# picotouch_synth.net
KiCad netlist of a schematic drawn in EAGLE
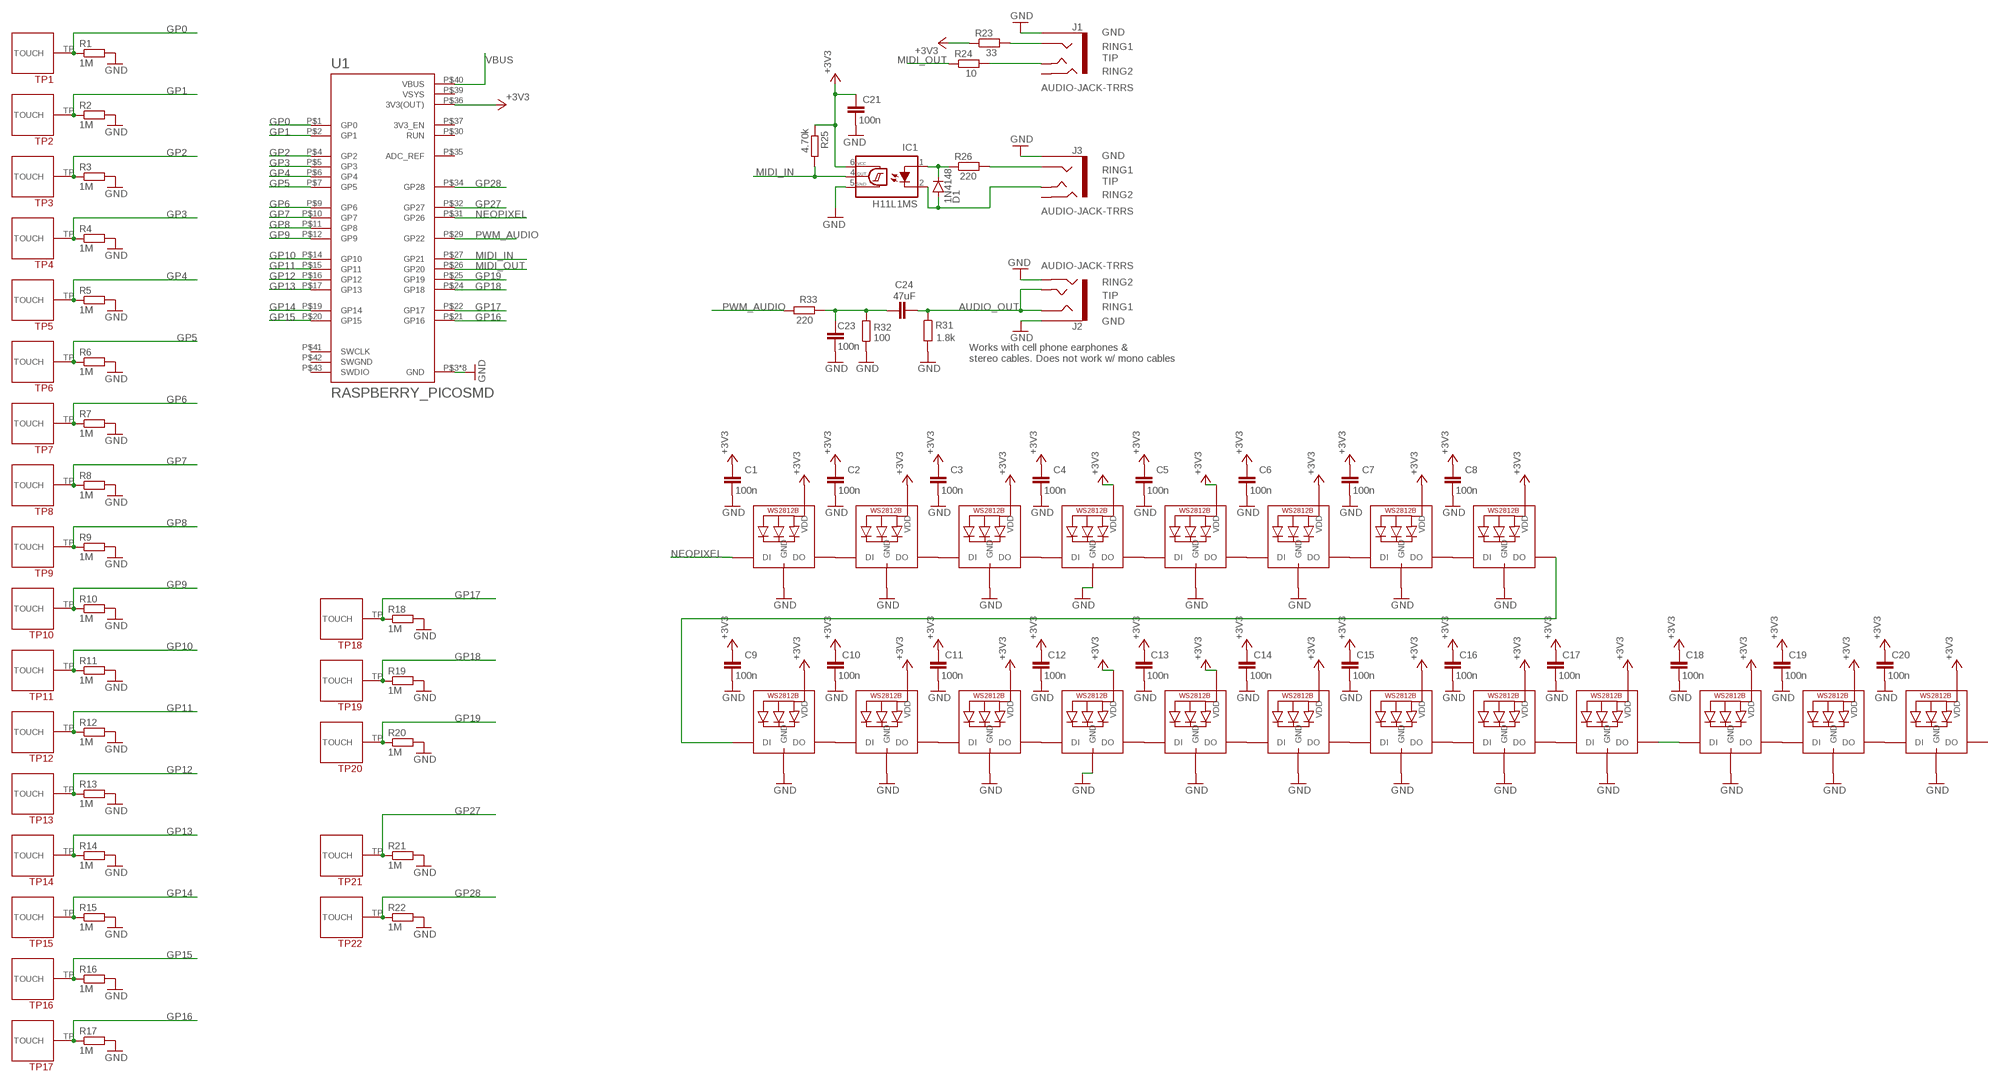
[diagram p0: schematic, sheet 1]

(export (version "E")
  (design (tool "Eeschema 10.0.6"))
  (components
    (comp (ref "C1")
      (value "100n")
      (footprint "eagle-import:C0603")
      (libsource (lib "eagle-import") (part "C-EUC0603"))
    )
    (comp (ref "C2")
      (value "100n")
      (footprint "eagle-import:C0603")
      (libsource (lib "eagle-import") (part "C-EUC0603"))
    )
    (comp (ref "C3")
      (value "100n")
      (footprint "eagle-import:C0603")
      (libsource (lib "eagle-import") (part "C-EUC0603"))
    )
    (comp (ref "C4")
      (value "100n")
      (footprint "eagle-import:C0603")
      (libsource (lib "eagle-import") (part "C-EUC0603"))
    )
    (comp (ref "C5")
      (value "100n")
      (footprint "eagle-import:C0603")
      (libsource (lib "eagle-import") (part "C-EUC0603"))
    )
    (comp (ref "C6")
      (value "100n")
      (footprint "eagle-import:C0603")
      (libsource (lib "eagle-import") (part "C-EUC0603"))
    )
    (comp (ref "C7")
      (value "100n")
      (footprint "eagle-import:C0603")
      (libsource (lib "eagle-import") (part "C-EUC0603"))
    )
    (comp (ref "C8")
      (value "100n")
      (footprint "eagle-import:C0603")
      (libsource (lib "eagle-import") (part "C-EUC0603"))
    )
    (comp (ref "C9")
      (value "100n")
      (footprint "eagle-import:C0603")
      (libsource (lib "eagle-import") (part "C-EUC0603"))
    )
    (comp (ref "C10")
      (value "100n")
      (footprint "eagle-import:C0603")
      (libsource (lib "eagle-import") (part "C-EUC0603"))
    )
    (comp (ref "C11")
      (value "100n")
      (footprint "eagle-import:C0603")
      (libsource (lib "eagle-import") (part "C-EUC0603"))
    )
    (comp (ref "C12")
      (value "100n")
      (footprint "eagle-import:C0603")
      (libsource (lib "eagle-import") (part "C-EUC0603"))
    )
    (comp (ref "C13")
      (value "100n")
      (footprint "eagle-import:C0603")
      (libsource (lib "eagle-import") (part "C-EUC0603"))
    )
    (comp (ref "C14")
      (value "100n")
      (footprint "eagle-import:C0603")
      (libsource (lib "eagle-import") (part "C-EUC0603"))
    )
    (comp (ref "C15")
      (value "100n")
      (footprint "eagle-import:C0603")
      (libsource (lib "eagle-import") (part "C-EUC0603"))
    )
    (comp (ref "C16")
      (value "100n")
      (footprint "eagle-import:C0603")
      (libsource (lib "eagle-import") (part "C-EUC0603"))
    )
    (comp (ref "C17")
      (value "100n")
      (footprint "eagle-import:C0603")
      (libsource (lib "eagle-import") (part "C-EUC0603"))
    )
    (comp (ref "C18")
      (value "100n")
      (footprint "eagle-import:C0603")
      (libsource (lib "eagle-import") (part "C-EUC0603"))
    )
    (comp (ref "C19")
      (value "100n")
      (footprint "eagle-import:C0603")
      (libsource (lib "eagle-import") (part "C-EUC0603"))
    )
    (comp (ref "C20")
      (value "100n")
      (footprint "eagle-import:C0603")
      (libsource (lib "eagle-import") (part "C-EUC0603"))
    )
    (comp (ref "C21")
      (value "100n")
      (footprint "eagle-import:C0603")
      (libsource (lib "eagle-import") (part "C-EUC0603"))
    )
    (comp (ref "C23")
      (value "100n")
      (footprint "eagle-import:C0603")
      (libsource (lib "eagle-import") (part "C-EUC0603"))
    )
    (comp (ref "C24")
      (value "47uF")
      (footprint "eagle-import:C0603")
      (libsource (lib "eagle-import") (part "C-EUC0603"))
    )
    (comp (ref "D1")
      (value "1N4148")
      (footprint "eagle-import:SOD123")
      (libsource (lib "eagle-import") (part "DIODE-SOD123"))
    )
    (comp (ref "IC1")
      (value "H11L1MS")
      (footprint "eagle-import:DIL6-SMD")
      (libsource (lib "eagle-import") (part "H11LMS1"))
    )
    (comp (ref "J1")
      (value "AUDIO-JACK-TRRS")
      (footprint "eagle-import:PJ-320D_SPARKFUN")
      (fields (field (name "MPN") "PJ-320D"))
      (libsource (lib "eagle-import") (part "AUDIO-JACK-TRRS"))
    )
    (comp (ref "J2")
      (value "AUDIO-JACK-TRRS")
      (footprint "eagle-import:PJ-320D_SPARKFUN")
      (fields (field (name "MPN") "PJ-320D") (field (name "LCSC") "C431535"))
      (libsource (lib "eagle-import") (part "AUDIO-JACK-TRRS"))
    )
    (comp (ref "J3")
      (value "AUDIO-JACK-TRRS")
      (footprint "eagle-import:PJ-320D_SPARKFUN")
      (fields (field (name "MPN") "PJ-320D"))
      (libsource (lib "eagle-import") (part "AUDIO-JACK-TRRS"))
    )
    (comp (ref "LED1")
      (value "WS2812B3535")
      (footprint "eagle-import:LED3535")
      (libsource (lib "eagle-import") (part "WS2812B3535"))
    )
    (comp (ref "LED2")
      (value "WS2812B3535")
      (footprint "eagle-import:LED3535")
      (libsource (lib "eagle-import") (part "WS2812B3535"))
    )
    (comp (ref "LED3")
      (value "WS2812B3535")
      (footprint "eagle-import:LED3535")
      (libsource (lib "eagle-import") (part "WS2812B3535"))
    )
    (comp (ref "LED4")
      (value "WS2812B3535")
      (footprint "eagle-import:LED3535")
      (libsource (lib "eagle-import") (part "WS2812B3535"))
    )
    (comp (ref "LED5")
      (value "WS2812B3535")
      (footprint "eagle-import:LED3535")
      (libsource (lib "eagle-import") (part "WS2812B3535"))
    )
    (comp (ref "LED6")
      (value "WS2812B3535")
      (footprint "eagle-import:LED3535")
      (libsource (lib "eagle-import") (part "WS2812B3535"))
    )
    (comp (ref "LED7")
      (value "WS2812B3535")
      (footprint "eagle-import:LED3535")
      (libsource (lib "eagle-import") (part "WS2812B3535"))
    )
    (comp (ref "LED8")
      (value "WS2812B3535")
      (footprint "eagle-import:LED3535")
      (libsource (lib "eagle-import") (part "WS2812B3535"))
    )
    (comp (ref "LED9")
      (value "WS2812B3535")
      (footprint "eagle-import:LED3535")
      (libsource (lib "eagle-import") (part "WS2812B3535"))
    )
    (comp (ref "LED10")
      (value "WS2812B3535")
      (footprint "eagle-import:LED3535")
      (libsource (lib "eagle-import") (part "WS2812B3535"))
    )
    (comp (ref "LED11")
      (value "WS2812B3535")
      (footprint "eagle-import:LED3535")
      (libsource (lib "eagle-import") (part "WS2812B3535"))
    )
    (comp (ref "LED12")
      (value "WS2812B3535")
      (footprint "eagle-import:LED3535")
      (libsource (lib "eagle-import") (part "WS2812B3535"))
    )
    (comp (ref "LED13")
      (value "WS2812B3535")
      (footprint "eagle-import:LED3535")
      (libsource (lib "eagle-import") (part "WS2812B3535"))
    )
    (comp (ref "LED14")
      (value "WS2812B3535")
      (footprint "eagle-import:LED3535")
      (libsource (lib "eagle-import") (part "WS2812B3535"))
    )
    (comp (ref "LED15")
      (value "WS2812B3535")
      (footprint "eagle-import:LED3535")
      (libsource (lib "eagle-import") (part "WS2812B3535"))
    )
    (comp (ref "LED16")
      (value "WS2812B3535")
      (footprint "eagle-import:LED3535")
      (libsource (lib "eagle-import") (part "WS2812B3535"))
    )
    (comp (ref "LED17")
      (value "WS2812B3535")
      (footprint "eagle-import:LED3535")
      (libsource (lib "eagle-import") (part "WS2812B3535"))
    )
    (comp (ref "LED18")
      (value "WS2812B3535")
      (footprint "eagle-import:LED3535")
      (libsource (lib "eagle-import") (part "WS2812B3535"))
    )
    (comp (ref "LED19")
      (value "WS2812B3535")
      (footprint "eagle-import:LED3535")
      (libsource (lib "eagle-import") (part "WS2812B3535"))
    )
    (comp (ref "LED20")
      (value "WS2812B3535")
      (footprint "eagle-import:LED3535")
      (libsource (lib "eagle-import") (part "WS2812B3535"))
    )
    (comp (ref "R1")
      (value "1M")
      (footprint "eagle-import:R0805")
      (libsource (lib "eagle-import") (part "R-EU_R0805"))
    )
    (comp (ref "R2")
      (value "1M")
      (footprint "eagle-import:R0805")
      (libsource (lib "eagle-import") (part "R-EU_R0805"))
    )
    (comp (ref "R3")
      (value "1M")
      (footprint "eagle-import:R0805")
      (libsource (lib "eagle-import") (part "R-EU_R0805"))
    )
    (comp (ref "R4")
      (value "1M")
      (footprint "eagle-import:R0805")
      (libsource (lib "eagle-import") (part "R-EU_R0805"))
    )
    (comp (ref "R5")
      (value "1M")
      (footprint "eagle-import:R0805")
      (libsource (lib "eagle-import") (part "R-EU_R0805"))
    )
    (comp (ref "R6")
      (value "1M")
      (footprint "eagle-import:R0805")
      (libsource (lib "eagle-import") (part "R-EU_R0805"))
    )
    (comp (ref "R7")
      (value "1M")
      (footprint "eagle-import:R0805")
      (libsource (lib "eagle-import") (part "R-EU_R0805"))
    )
    (comp (ref "R8")
      (value "1M")
      (footprint "eagle-import:R0805")
      (libsource (lib "eagle-import") (part "R-EU_R0805"))
    )
    (comp (ref "R9")
      (value "1M")
      (footprint "eagle-import:R0805")
      (libsource (lib "eagle-import") (part "R-EU_R0805"))
    )
    (comp (ref "R10")
      (value "1M")
      (footprint "eagle-import:R0805")
      (libsource (lib "eagle-import") (part "R-EU_R0805"))
    )
    (comp (ref "R11")
      (value "1M")
      (footprint "eagle-import:R0805")
      (libsource (lib "eagle-import") (part "R-EU_R0805"))
    )
    (comp (ref "R12")
      (value "1M")
      (footprint "eagle-import:R0805")
      (libsource (lib "eagle-import") (part "R-EU_R0805"))
    )
    (comp (ref "R13")
      (value "1M")
      (footprint "eagle-import:R0805")
      (libsource (lib "eagle-import") (part "R-EU_R0805"))
    )
    (comp (ref "R14")
      (value "1M")
      (footprint "eagle-import:R0805")
      (libsource (lib "eagle-import") (part "R-EU_R0805"))
    )
    (comp (ref "R15")
      (value "1M")
      (footprint "eagle-import:R0805")
      (libsource (lib "eagle-import") (part "R-EU_R0805"))
    )
    (comp (ref "R16")
      (value "1M")
      (footprint "eagle-import:R0805")
      (libsource (lib "eagle-import") (part "R-EU_R0805"))
    )
    (comp (ref "R17")
      (value "1M")
      (footprint "eagle-import:R0805")
      (libsource (lib "eagle-import") (part "R-EU_R0805"))
    )
    (comp (ref "R18")
      (value "1M")
      (footprint "eagle-import:R0603")
      (libsource (lib "eagle-import") (part "R-EU_R0603"))
    )
    (comp (ref "R19")
      (value "1M")
      (footprint "eagle-import:R0603")
      (libsource (lib "eagle-import") (part "R-EU_R0603"))
    )
    (comp (ref "R20")
      (value "1M")
      (footprint "eagle-import:R0603")
      (libsource (lib "eagle-import") (part "R-EU_R0603"))
    )
    (comp (ref "R21")
      (value "1M")
      (footprint "eagle-import:R0603")
      (libsource (lib "eagle-import") (part "R-EU_R0603"))
    )
    (comp (ref "R22")
      (value "1M")
      (footprint "eagle-import:R0603")
      (libsource (lib "eagle-import") (part "R-EU_R0603"))
    )
    (comp (ref "R23")
      (value "33")
      (footprint "eagle-import:R0603")
      (libsource (lib "eagle-import") (part "R-EU_R0603"))
    )
    (comp (ref "R24")
      (value "10")
      (footprint "eagle-import:R0603")
      (libsource (lib "eagle-import") (part "R-EU_R0603"))
    )
    (comp (ref "R25")
      (value "4.70k")
      (footprint "eagle-import:R0603")
      (libsource (lib "eagle-import") (part "R-EU_R0603"))
    )
    (comp (ref "R26")
      (value "220")
      (footprint "eagle-import:R0603")
      (libsource (lib "eagle-import") (part "R-EU_R0603"))
    )
    (comp (ref "R31")
      (value "1.8k")
      (footprint "eagle-import:R0603")
      (libsource (lib "eagle-import") (part "R-EU_R0603"))
    )
    (comp (ref "R32")
      (value "100")
      (footprint "eagle-import:R0603")
      (libsource (lib "eagle-import") (part "R-EU_R0603"))
    )
    (comp (ref "R33")
      (value "220")
      (footprint "eagle-import:R0603")
      (libsource (lib "eagle-import") (part "R-EU_R0603"))
    )
    (comp (ref "TP1")
      (value "TOUCHPADA")
      (footprint "eagle-import:TOUCHPADA")
      (libsource (lib "eagle-import") (part "TOUCHPADA"))
    )
    (comp (ref "TP2")
      (value "TOUCHPADA")
      (footprint "eagle-import:TOUCHPADA")
      (libsource (lib "eagle-import") (part "TOUCHPADA"))
    )
    (comp (ref "TP3")
      (value "TOUCHPADA")
      (footprint "eagle-import:TOUCHPADA")
      (libsource (lib "eagle-import") (part "TOUCHPADA"))
    )
    (comp (ref "TP4")
      (value "TOUCHPADA")
      (footprint "eagle-import:TOUCHPADA")
      (libsource (lib "eagle-import") (part "TOUCHPADA"))
    )
    (comp (ref "TP5")
      (value "TOUCHPADA")
      (footprint "eagle-import:TOUCHPADA")
      (libsource (lib "eagle-import") (part "TOUCHPADA"))
    )
    (comp (ref "TP6")
      (value "TOUCHPADA")
      (footprint "eagle-import:TOUCHPADA")
      (libsource (lib "eagle-import") (part "TOUCHPADA"))
    )
    (comp (ref "TP7")
      (value "TOUCHPADA")
      (footprint "eagle-import:TOUCHPADA")
      (libsource (lib "eagle-import") (part "TOUCHPADA"))
    )
    (comp (ref "TP8")
      (value "TOUCHPADA")
      (footprint "eagle-import:TOUCHPADA")
      (libsource (lib "eagle-import") (part "TOUCHPADA"))
    )
    (comp (ref "TP9")
      (value "TOUCHPADA")
      (footprint "eagle-import:TOUCHPADA")
      (libsource (lib "eagle-import") (part "TOUCHPADA"))
    )
    (comp (ref "TP10")
      (value "TOUCHPADA")
      (footprint "eagle-import:TOUCHPADA")
      (libsource (lib "eagle-import") (part "TOUCHPADA"))
    )
    (comp (ref "TP11")
      (value "TOUCHPADA")
      (footprint "eagle-import:TOUCHPADA")
      (libsource (lib "eagle-import") (part "TOUCHPADA"))
    )
    (comp (ref "TP12")
      (value "TOUCHPADA")
      (footprint "eagle-import:TOUCHPADA")
      (libsource (lib "eagle-import") (part "TOUCHPADA"))
    )
    (comp (ref "TP13")
      (value "TOUCHPADA")
      (footprint "eagle-import:TOUCHPADA")
      (libsource (lib "eagle-import") (part "TOUCHPADA"))
    )
    (comp (ref "TP14")
      (value "TOUCHPADA")
      (footprint "eagle-import:TOUCHPADA")
      (libsource (lib "eagle-import") (part "TOUCHPADA"))
    )
    (comp (ref "TP15")
      (value "TOUCHPADA")
      (footprint "eagle-import:TOUCHPADA")
      (libsource (lib "eagle-import") (part "TOUCHPADA"))
    )
    (comp (ref "TP16")
      (value "TOUCHPADA")
      (footprint "eagle-import:TOUCHPADA")
      (libsource (lib "eagle-import") (part "TOUCHPADA"))
    )
    (comp (ref "TP17")
      (value "TOUCHPADA")
      (footprint "eagle-import:TOUCHPADA")
      (libsource (lib "eagle-import") (part "TOUCHPADA"))
    )
    (comp (ref "TP18")
      (value "TOUCHPADB")
      (footprint "eagle-import:TOUCHPADB")
      (libsource (lib "eagle-import") (part "TOUCHPADB"))
    )
    (comp (ref "TP19")
      (value "TOUCHPADB")
      (footprint "eagle-import:TOUCHPADB")
      (libsource (lib "eagle-import") (part "TOUCHPADB"))
    )
    (comp (ref "TP20")
      (value "TOUCHPADB")
      (footprint "eagle-import:TOUCHPADB")
      (libsource (lib "eagle-import") (part "TOUCHPADB"))
    )
    (comp (ref "TP21")
      (value "TOUCHPADB")
      (footprint "eagle-import:TOUCHPADB")
      (libsource (lib "eagle-import") (part "TOUCHPADB"))
    )
    (comp (ref "TP22")
      (value "TOUCHPADB")
      (footprint "eagle-import:TOUCHPADB")
      (libsource (lib "eagle-import") (part "TOUCHPADB"))
    )
    (comp (ref "U1")
      (value "RASPBERRY_PICOSMD")
      (footprint "eagle-import:PICO-PKG-SMD")
      (libsource (lib "eagle-import") (part "RASPBERRY_PICOSMD"))
    )
  )
  (nets
    (net (code "1") (name "+3V3") (class "Default")
      (node (ref "C1") (pin "1") (pinfunction "1_1") (pintype "passive"))
      (node (ref "C10") (pin "1") (pinfunction "1_1") (pintype "passive"))
      (node (ref "C11") (pin "1") (pinfunction "1_1") (pintype "passive"))
      (node (ref "C12") (pin "1") (pinfunction "1_1") (pintype "passive"))
      (node (ref "C13") (pin "1") (pinfunction "1_1") (pintype "passive"))
      (node (ref "C14") (pin "1") (pinfunction "1_1") (pintype "passive"))
      (node (ref "C15") (pin "1") (pinfunction "1_1") (pintype "passive"))
      (node (ref "C16") (pin "1") (pinfunction "1_1") (pintype "passive"))
      (node (ref "C17") (pin "1") (pinfunction "1_1") (pintype "passive"))
      (node (ref "C18") (pin "1") (pinfunction "1_1") (pintype "passive"))
      (node (ref "C19") (pin "1") (pinfunction "1_1") (pintype "passive"))
      (node (ref "C2") (pin "1") (pinfunction "1_1") (pintype "passive"))
      (node (ref "C20") (pin "1") (pinfunction "1_1") (pintype "passive"))
      (node (ref "C21") (pin "1") (pinfunction "1_1") (pintype "passive"))
      (node (ref "C3") (pin "1") (pinfunction "1_1") (pintype "passive"))
      (node (ref "C4") (pin "1") (pinfunction "1_1") (pintype "passive"))
      (node (ref "C5") (pin "1") (pinfunction "1_1") (pintype "passive"))
      (node (ref "C6") (pin "1") (pinfunction "1_1") (pintype "passive"))
      (node (ref "C7") (pin "1") (pinfunction "1_1") (pintype "passive"))
      (node (ref "C8") (pin "1") (pinfunction "1_1") (pintype "passive"))
      (node (ref "C9") (pin "1") (pinfunction "1_1") (pintype "passive"))
      (node (ref "IC1") (pin "6") (pinfunction "VCC_6") (pintype "power_in"))
      (node (ref "LED1") (pin "2") (pinfunction "VDD_2") (pintype "power_in"))
      (node (ref "LED10") (pin "2") (pinfunction "VDD_2") (pintype "power_in"))
      (node (ref "LED11") (pin "2") (pinfunction "VDD_2") (pintype "power_in"))
      (node (ref "LED12") (pin "2") (pinfunction "VDD_2") (pintype "power_in"))
      (node (ref "LED13") (pin "2") (pinfunction "VDD_2") (pintype "power_in"))
      (node (ref "LED14") (pin "2") (pinfunction "VDD_2") (pintype "power_in"))
      (node (ref "LED15") (pin "2") (pinfunction "VDD_2") (pintype "power_in"))
      (node (ref "LED16") (pin "2") (pinfunction "VDD_2") (pintype "power_in"))
      (node (ref "LED17") (pin "2") (pinfunction "VDD_2") (pintype "power_in"))
      (node (ref "LED18") (pin "2") (pinfunction "VDD_2") (pintype "power_in"))
      (node (ref "LED19") (pin "2") (pinfunction "VDD_2") (pintype "power_in"))
      (node (ref "LED2") (pin "2") (pinfunction "VDD_2") (pintype "power_in"))
      (node (ref "LED20") (pin "2") (pinfunction "VDD_2") (pintype "power_in"))
      (node (ref "LED3") (pin "2") (pinfunction "VDD_2") (pintype "power_in"))
      (node (ref "LED4") (pin "2") (pinfunction "VDD_2") (pintype "power_in"))
      (node (ref "LED5") (pin "2") (pinfunction "VDD_2") (pintype "power_in"))
      (node (ref "LED6") (pin "2") (pinfunction "VDD_2") (pintype "power_in"))
      (node (ref "LED7") (pin "2") (pinfunction "VDD_2") (pintype "power_in"))
      (node (ref "LED8") (pin "2") (pinfunction "VDD_2") (pintype "power_in"))
      (node (ref "LED9") (pin "2") (pinfunction "VDD_2") (pintype "power_in"))
      (node (ref "R23") (pin "1") (pinfunction "1_1") (pintype "passive"))
      (node (ref "R25") (pin "1") (pinfunction "1_1") (pintype "passive"))
      (node (ref "U1") (pin "P$36") (pinfunction "3V3(OUT)_P$36") (pintype "power_in"))
    )
    (net (code "2") (name "/AUDIO_OUT") (class "Default")
      (node (ref "C24") (pin "2") (pinfunction "2_2") (pintype "passive"))
      (node (ref "J2") (pin "RING1") (pinfunction "RING1_RING1") (pintype "bidirectional"))
      (node (ref "J2") (pin "TIP") (pinfunction "TIP_TIP") (pintype "bidirectional"))
      (node (ref "R31") (pin "1") (pinfunction "1_1") (pintype "passive"))
    )
    (net (code "3") (name "/GP0") (class "Default")
      (node (ref "R1") (pin "1") (pinfunction "1_1") (pintype "passive"))
      (node (ref "TP1") (pin "TP") (pinfunction "TOUCH_TP") (pintype "bidirectional"))
      (node (ref "U1") (pin "P$1") (pinfunction "GP0_P$1") (pintype "bidirectional"))
    )
    (net (code "4") (name "/GP1") (class "Default")
      (node (ref "R2") (pin "1") (pinfunction "1_1") (pintype "passive"))
      (node (ref "TP2") (pin "TP") (pinfunction "TOUCH_TP") (pintype "bidirectional"))
      (node (ref "U1") (pin "P$2") (pinfunction "GP1_P$2") (pintype "bidirectional"))
    )
    (net (code "5") (name "/GP2") (class "Default")
      (node (ref "R3") (pin "1") (pinfunction "1_1") (pintype "passive"))
      (node (ref "TP3") (pin "TP") (pinfunction "TOUCH_TP") (pintype "bidirectional"))
      (node (ref "U1") (pin "P$4") (pinfunction "GP2_P$4") (pintype "bidirectional"))
    )
    (net (code "6") (name "/GP3") (class "Default")
      (node (ref "R4") (pin "1") (pinfunction "1_1") (pintype "passive"))
      (node (ref "TP4") (pin "TP") (pinfunction "TOUCH_TP") (pintype "bidirectional"))
      (node (ref "U1") (pin "P$5") (pinfunction "GP3_P$5") (pintype "bidirectional"))
    )
    (net (code "7") (name "/GP4") (class "Default")
      (node (ref "R5") (pin "1") (pinfunction "1_1") (pintype "passive"))
      (node (ref "TP5") (pin "TP") (pinfunction "TOUCH_TP") (pintype "bidirectional"))
      (node (ref "U1") (pin "P$6") (pinfunction "GP4_P$6") (pintype "bidirectional"))
    )
    (net (code "8") (name "/GP5") (class "Default")
      (node (ref "R6") (pin "1") (pinfunction "1_1") (pintype "passive"))
      (node (ref "TP6") (pin "TP") (pinfunction "TOUCH_TP") (pintype "bidirectional"))
      (node (ref "U1") (pin "P$7") (pinfunction "GP5_P$7") (pintype "bidirectional"))
    )
    (net (code "9") (name "/GP6") (class "Default")
      (node (ref "R7") (pin "1") (pinfunction "1_1") (pintype "passive"))
      (node (ref "TP7") (pin "TP") (pinfunction "TOUCH_TP") (pintype "bidirectional"))
      (node (ref "U1") (pin "P$9") (pinfunction "GP6_P$9") (pintype "bidirectional"))
    )
    (net (code "10") (name "/GP7") (class "Default")
      (node (ref "R8") (pin "1") (pinfunction "1_1") (pintype "passive"))
      (node (ref "TP8") (pin "TP") (pinfunction "TOUCH_TP") (pintype "bidirectional"))
      (node (ref "U1") (pin "P$10") (pinfunction "GP7_P$10") (pintype "bidirectional"))
    )
    (net (code "11") (name "/GP8") (class "Default")
      (node (ref "R9") (pin "1") (pinfunction "1_1") (pintype "passive"))
      (node (ref "TP9") (pin "TP") (pinfunction "TOUCH_TP") (pintype "bidirectional"))
      (node (ref "U1") (pin "P$11") (pinfunction "GP8_P$11") (pintype "bidirectional"))
    )
    (net (code "12") (name "/GP9") (class "Default")
      (node (ref "R10") (pin "1") (pinfunction "1_1") (pintype "passive"))
      (node (ref "TP10") (pin "TP") (pinfunction "TOUCH_TP") (pintype "bidirectional"))
      (node (ref "U1") (pin "P$12") (pinfunction "GP9_P$12") (pintype "bidirectional"))
    )
    (net (code "13") (name "/GP10") (class "Default")
      (node (ref "R11") (pin "1") (pinfunction "1_1") (pintype "passive"))
      (node (ref "TP11") (pin "TP") (pinfunction "TOUCH_TP") (pintype "bidirectional"))
      (node (ref "U1") (pin "P$14") (pinfunction "GP10_P$14") (pintype "bidirectional"))
    )
    (net (code "14") (name "/GP11") (class "Default")
      (node (ref "R12") (pin "1") (pinfunction "1_1") (pintype "passive"))
      (node (ref "TP12") (pin "TP") (pinfunction "TOUCH_TP") (pintype "bidirectional"))
      (node (ref "U1") (pin "P$15") (pinfunction "GP11_P$15") (pintype "bidirectional"))
    )
    (net (code "15") (name "/GP12") (class "Default")
      (node (ref "R13") (pin "1") (pinfunction "1_1") (pintype "passive"))
      (node (ref "TP13") (pin "TP") (pinfunction "TOUCH_TP") (pintype "bidirectional"))
      (node (ref "U1") (pin "P$16") (pinfunction "GP12_P$16") (pintype "bidirectional"))
    )
    (net (code "16") (name "/GP13") (class "Default")
      (node (ref "R14") (pin "1") (pinfunction "1_1") (pintype "passive"))
      (node (ref "TP14") (pin "TP") (pinfunction "TOUCH_TP") (pintype "bidirectional"))
      (node (ref "U1") (pin "P$17") (pinfunction "GP13_P$17") (pintype "bidirectional"))
    )
    (net (code "17") (name "/GP14") (class "Default")
      (node (ref "R15") (pin "1") (pinfunction "1_1") (pintype "passive"))
      (node (ref "TP15") (pin "TP") (pinfunction "TOUCH_TP") (pintype "bidirectional"))
      (node (ref "U1") (pin "P$19") (pinfunction "GP14_P$19") (pintype "bidirectional"))
    )
    (net (code "18") (name "/GP15") (class "Default")
      (node (ref "R16") (pin "1") (pinfunction "1_1") (pintype "passive"))
      (node (ref "TP16") (pin "TP") (pinfunction "TOUCH_TP") (pintype "bidirectional"))
      (node (ref "U1") (pin "P$20") (pinfunction "GP15_P$20") (pintype "bidirectional"))
    )
    (net (code "19") (name "/GP16") (class "Default")
      (node (ref "R17") (pin "1") (pinfunction "1_1") (pintype "passive"))
      (node (ref "TP17") (pin "TP") (pinfunction "TOUCH_TP") (pintype "bidirectional"))
      (node (ref "U1") (pin "P$21") (pinfunction "GP16_P$21") (pintype "bidirectional"))
    )
    (net (code "20") (name "/GP17") (class "Default")
      (node (ref "R18") (pin "1") (pinfunction "1_1") (pintype "passive"))
      (node (ref "TP18") (pin "TP") (pinfunction "TOUCH_TP") (pintype "bidirectional"))
      (node (ref "U1") (pin "P$22") (pinfunction "GP17_P$22") (pintype "bidirectional"))
    )
    (net (code "21") (name "/GP18") (class "Default")
      (node (ref "R19") (pin "1") (pinfunction "1_1") (pintype "passive"))
      (node (ref "TP19") (pin "TP") (pinfunction "TOUCH_TP") (pintype "bidirectional"))
      (node (ref "U1") (pin "P$24") (pinfunction "GP18_P$24") (pintype "bidirectional"))
    )
    (net (code "22") (name "/GP19") (class "Default")
      (node (ref "R20") (pin "1") (pinfunction "1_1") (pintype "passive"))
      (node (ref "TP20") (pin "TP") (pinfunction "TOUCH_TP") (pintype "bidirectional"))
      (node (ref "U1") (pin "P$25") (pinfunction "GP19_P$25") (pintype "bidirectional"))
    )
    (net (code "23") (name "/GP27") (class "Default")
      (node (ref "R21") (pin "1") (pinfunction "1_1") (pintype "passive"))
      (node (ref "TP21") (pin "TP") (pinfunction "TOUCH_TP") (pintype "bidirectional"))
      (node (ref "U1") (pin "P$32") (pinfunction "GP27_P$32") (pintype "bidirectional"))
    )
    (net (code "24") (name "/GP28") (class "Default")
      (node (ref "R22") (pin "1") (pinfunction "1_1") (pintype "passive"))
      (node (ref "TP22") (pin "TP") (pinfunction "TOUCH_TP") (pintype "bidirectional"))
      (node (ref "U1") (pin "P$34") (pinfunction "GP28_P$34") (pintype "bidirectional"))
    )
    (net (code "25") (name "/MIDI_IN") (class "Default")
      (node (ref "IC1") (pin "4") (pinfunction "OUT_4") (pintype "output"))
      (node (ref "R25") (pin "2") (pinfunction "2_2") (pintype "passive"))
      (node (ref "U1") (pin "P$27") (pinfunction "GP21_P$27") (pintype "bidirectional"))
    )
    (net (code "26") (name "/MIDI_OUT") (class "Default")
      (node (ref "R24") (pin "1") (pinfunction "1_1") (pintype "passive"))
      (node (ref "U1") (pin "P$26") (pinfunction "GP20_P$26") (pintype "bidirectional"))
    )
    (net (code "27") (name "/NEOPIXEL") (class "Default")
      (node (ref "LED1") (pin "1") (pinfunction "DI_1") (pintype "input"))
      (node (ref "U1") (pin "P$31") (pinfunction "GP26_P$31") (pintype "bidirectional"))
    )
    (net (code "28") (name "/PWM_AUDIO") (class "Default")
      (node (ref "R33") (pin "2") (pinfunction "2_2") (pintype "passive"))
      (node (ref "U1") (pin "P$29") (pinfunction "GP22_P$29") (pintype "bidirectional"))
    )
    (net (code "29") (name "/SWGND") (class "Default")
      (node (ref "U1") (pin "P$42") (pinfunction "SWGND_P$42") (pintype "power_in"))
    )
    (net (code "30") (name "/VBUS") (class "Default")
      (node (ref "U1") (pin "P$40") (pinfunction "VBUS_P$40") (pintype "power_in"))
    )
    (net (code "31") (name "/VSYS") (class "Default")
      (node (ref "U1") (pin "P$39") (pinfunction "VSYS_P$39") (pintype "power_in"))
    )
    (net (code "32") (name "GND") (class "Default")
      (node (ref "C1") (pin "2") (pinfunction "2_2") (pintype "passive"))
      (node (ref "C10") (pin "2") (pinfunction "2_2") (pintype "passive"))
      (node (ref "C11") (pin "2") (pinfunction "2_2") (pintype "passive"))
      (node (ref "C12") (pin "2") (pinfunction "2_2") (pintype "passive"))
      (node (ref "C13") (pin "2") (pinfunction "2_2") (pintype "passive"))
      (node (ref "C14") (pin "2") (pinfunction "2_2") (pintype "passive"))
      (node (ref "C15") (pin "2") (pinfunction "2_2") (pintype "passive"))
      (node (ref "C16") (pin "2") (pinfunction "2_2") (pintype "passive"))
      (node (ref "C17") (pin "2") (pinfunction "2_2") (pintype "passive"))
      (node (ref "C18") (pin "2") (pinfunction "2_2") (pintype "passive"))
      (node (ref "C19") (pin "2") (pinfunction "2_2") (pintype "passive"))
      (node (ref "C2") (pin "2") (pinfunction "2_2") (pintype "passive"))
      (node (ref "C20") (pin "2") (pinfunction "2_2") (pintype "passive"))
      (node (ref "C21") (pin "2") (pinfunction "2_2") (pintype "passive"))
      (node (ref "C23") (pin "2") (pinfunction "2_2") (pintype "passive"))
      (node (ref "C3") (pin "2") (pinfunction "2_2") (pintype "passive"))
      (node (ref "C4") (pin "2") (pinfunction "2_2") (pintype "passive"))
      (node (ref "C5") (pin "2") (pinfunction "2_2") (pintype "passive"))
      (node (ref "C6") (pin "2") (pinfunction "2_2") (pintype "passive"))
      (node (ref "C7") (pin "2") (pinfunction "2_2") (pintype "passive"))
      (node (ref "C8") (pin "2") (pinfunction "2_2") (pintype "passive"))
      (node (ref "C9") (pin "2") (pinfunction "2_2") (pintype "passive"))
      (node (ref "IC1") (pin "5") (pinfunction "GND_5") (pintype "power_in"))
      (node (ref "J1") (pin "EARTH") (pinfunction "EARTH_EARTH") (pintype "bidirectional"))
      (node (ref "J2") (pin "EARTH") (pinfunction "EARTH_EARTH") (pintype "bidirectional"))
      (node (ref "J2") (pin "RING2") (pinfunction "RING2_RING2") (pintype "bidirectional"))
      (node (ref "J3") (pin "EARTH") (pinfunction "EARTH_EARTH") (pintype "bidirectional"))
      (node (ref "LED1") (pin "4") (pinfunction "GND_4") (pintype "power_in"))
      (node (ref "LED10") (pin "4") (pinfunction "GND_4") (pintype "power_in"))
      (node (ref "LED11") (pin "4") (pinfunction "GND_4") (pintype "power_in"))
      (node (ref "LED12") (pin "4") (pinfunction "GND_4") (pintype "power_in"))
      (node (ref "LED13") (pin "4") (pinfunction "GND_4") (pintype "power_in"))
      (node (ref "LED14") (pin "4") (pinfunction "GND_4") (pintype "power_in"))
      (node (ref "LED15") (pin "4") (pinfunction "GND_4") (pintype "power_in"))
      (node (ref "LED16") (pin "4") (pinfunction "GND_4") (pintype "power_in"))
      (node (ref "LED17") (pin "4") (pinfunction "GND_4") (pintype "power_in"))
      (node (ref "LED18") (pin "4") (pinfunction "GND_4") (pintype "power_in"))
      (node (ref "LED19") (pin "4") (pinfunction "GND_4") (pintype "power_in"))
      (node (ref "LED2") (pin "4") (pinfunction "GND_4") (pintype "power_in"))
      (node (ref "LED20") (pin "4") (pinfunction "GND_4") (pintype "power_in"))
      (node (ref "LED3") (pin "4") (pinfunction "GND_4") (pintype "power_in"))
      (node (ref "LED4") (pin "4") (pinfunction "GND_4") (pintype "power_in"))
      (node (ref "LED5") (pin "4") (pinfunction "GND_4") (pintype "power_in"))
      (node (ref "LED6") (pin "4") (pinfunction "GND_4") (pintype "power_in"))
      (node (ref "LED7") (pin "4") (pinfunction "GND_4") (pintype "power_in"))
      (node (ref "LED8") (pin "4") (pinfunction "GND_4") (pintype "power_in"))
      (node (ref "LED9") (pin "4") (pinfunction "GND_4") (pintype "power_in"))
      (node (ref "R1") (pin "2") (pinfunction "2_2") (pintype "passive"))
      (node (ref "R10") (pin "2") (pinfunction "2_2") (pintype "passive"))
      (node (ref "R11") (pin "2") (pinfunction "2_2") (pintype "passive"))
      (node (ref "R12") (pin "2") (pinfunction "2_2") (pintype "passive"))
      (node (ref "R13") (pin "2") (pinfunction "2_2") (pintype "passive"))
      (node (ref "R14") (pin "2") (pinfunction "2_2") (pintype "passive"))
      (node (ref "R15") (pin "2") (pinfunction "2_2") (pintype "passive"))
      (node (ref "R16") (pin "2") (pinfunction "2_2") (pintype "passive"))
      (node (ref "R17") (pin "2") (pinfunction "2_2") (pintype "passive"))
      (node (ref "R18") (pin "2") (pinfunction "2_2") (pintype "passive"))
      (node (ref "R19") (pin "2") (pinfunction "2_2") (pintype "passive"))
      (node (ref "R2") (pin "2") (pinfunction "2_2") (pintype "passive"))
      (node (ref "R20") (pin "2") (pinfunction "2_2") (pintype "passive"))
      (node (ref "R21") (pin "2") (pinfunction "2_2") (pintype "passive"))
      (node (ref "R22") (pin "2") (pinfunction "2_2") (pintype "passive"))
      (node (ref "R3") (pin "2") (pinfunction "2_2") (pintype "passive"))
      (node (ref "R31") (pin "2") (pinfunction "2_2") (pintype "passive"))
      (node (ref "R32") (pin "1") (pinfunction "1_1") (pintype "passive"))
      (node (ref "R4") (pin "2") (pinfunction "2_2") (pintype "passive"))
      (node (ref "R5") (pin "2") (pinfunction "2_2") (pintype "passive"))
      (node (ref "R6") (pin "2") (pinfunction "2_2") (pintype "passive"))
      (node (ref "R7") (pin "2") (pinfunction "2_2") (pintype "passive"))
      (node (ref "R8") (pin "2") (pinfunction "2_2") (pintype "passive"))
      (node (ref "R9") (pin "2") (pinfunction "2_2") (pintype "passive"))
      (node (ref "U1") (pin "P$13") (pinfunction "GND_P$13") (pintype "power_in"))
      (node (ref "U1") (pin "P$18") (pinfunction "GND_P$18") (pintype "power_in"))
      (node (ref "U1") (pin "P$23") (pinfunction "GND_P$23") (pintype "power_in"))
      (node (ref "U1") (pin "P$28") (pinfunction "GND_P$28") (pintype "power_in"))
      (node (ref "U1") (pin "P$3") (pinfunction "GND_P$3") (pintype "power_in"))
      (node (ref "U1") (pin "P$33") (pinfunction "GND_P$33") (pintype "power_in"))
      (node (ref "U1") (pin "P$38") (pinfunction "GND_P$38") (pintype "power_in"))
      (node (ref "U1") (pin "P$8") (pinfunction "GND_P$8") (pintype "power_in"))
    )
    (net (code "33") (name "Net-(C23-Pad1)") (class "Default")
      (node (ref "C23") (pin "1") (pinfunction "1_1") (pintype "passive"))
      (node (ref "C24") (pin "1") (pinfunction "1_1") (pintype "passive"))
      (node (ref "R32") (pin "2") (pinfunction "2_2") (pintype "passive"))
      (node (ref "R33") (pin "1") (pinfunction "1_1") (pintype "passive"))
    )
    (net (code "34") (name "Net-(IC1-A)") (class "Default")
      (node (ref "D1") (pin "C") (pinfunction "C_C") (pintype "passive"))
      (node (ref "IC1") (pin "1") (pinfunction "A_1") (pintype "passive"))
      (node (ref "R26") (pin "1") (pinfunction "1_1") (pintype "passive"))
    )
    (net (code "35") (name "Net-(IC1-C)") (class "Default")
      (node (ref "D1") (pin "A") (pinfunction "A_A") (pintype "passive"))
      (node (ref "IC1") (pin "2") (pinfunction "C_2") (pintype "passive"))
      (node (ref "J3") (pin "TIP") (pinfunction "TIP_TIP") (pintype "bidirectional"))
    )
    (net (code "36") (name "Net-(J1-PadRING1)") (class "Default")
      (node (ref "J1") (pin "RING1") (pinfunction "RING1_RING1") (pintype "bidirectional"))
      (node (ref "R23") (pin "2") (pinfunction "2_2") (pintype "passive"))
    )
    (net (code "37") (name "Net-(J1-PadTIP)") (class "Default")
      (node (ref "J1") (pin "TIP") (pinfunction "TIP_TIP") (pintype "bidirectional"))
      (node (ref "R24") (pin "2") (pinfunction "2_2") (pintype "passive"))
    )
    (net (code "38") (name "Net-(J3-PadRING1)") (class "Default")
      (node (ref "J3") (pin "RING1") (pinfunction "RING1_RING1") (pintype "bidirectional"))
      (node (ref "R26") (pin "2") (pinfunction "2_2") (pintype "passive"))
    )
    (net (code "39") (name "Net-(LED1-DO)") (class "Default")
      (node (ref "LED1") (pin "3") (pinfunction "DO_3") (pintype "output"))
      (node (ref "LED2") (pin "1") (pinfunction "DI_1") (pintype "input"))
    )
    (net (code "40") (name "Net-(LED2-DO)") (class "Default")
      (node (ref "LED2") (pin "3") (pinfunction "DO_3") (pintype "output"))
      (node (ref "LED3") (pin "1") (pinfunction "DI_1") (pintype "input"))
    )
    (net (code "41") (name "Net-(LED3-DO)") (class "Default")
      (node (ref "LED3") (pin "3") (pinfunction "DO_3") (pintype "output"))
      (node (ref "LED4") (pin "1") (pinfunction "DI_1") (pintype "input"))
    )
    (net (code "42") (name "Net-(LED4-DO)") (class "Default")
      (node (ref "LED4") (pin "3") (pinfunction "DO_3") (pintype "output"))
      (node (ref "LED5") (pin "1") (pinfunction "DI_1") (pintype "input"))
    )
    (net (code "43") (name "Net-(LED5-DO)") (class "Default")
      (node (ref "LED5") (pin "3") (pinfunction "DO_3") (pintype "output"))
      (node (ref "LED6") (pin "1") (pinfunction "DI_1") (pintype "input"))
    )
    (net (code "44") (name "Net-(LED6-DO)") (class "Default")
      (node (ref "LED6") (pin "3") (pinfunction "DO_3") (pintype "output"))
      (node (ref "LED7") (pin "1") (pinfunction "DI_1") (pintype "input"))
    )
    (net (code "45") (name "Net-(LED7-DO)") (class "Default")
      (node (ref "LED7") (pin "3") (pinfunction "DO_3") (pintype "output"))
      (node (ref "LED8") (pin "1") (pinfunction "DI_1") (pintype "input"))
    )
    (net (code "46") (name "Net-(LED8-DO)") (class "Default")
      (node (ref "LED8") (pin "3") (pinfunction "DO_3") (pintype "output"))
      (node (ref "LED9") (pin "1") (pinfunction "DI_1") (pintype "input"))
    )
    (net (code "47") (name "Net-(LED10-DI)") (class "Default")
      (node (ref "LED10") (pin "1") (pinfunction "DI_1") (pintype "input"))
      (node (ref "LED9") (pin "3") (pinfunction "DO_3") (pintype "output"))
    )
    (net (code "48") (name "Net-(LED10-DO)") (class "Default")
      (node (ref "LED10") (pin "3") (pinfunction "DO_3") (pintype "output"))
      (node (ref "LED11") (pin "1") (pinfunction "DI_1") (pintype "input"))
    )
    (net (code "49") (name "Net-(LED11-DO)") (class "Default")
      (node (ref "LED11") (pin "3") (pinfunction "DO_3") (pintype "output"))
      (node (ref "LED12") (pin "1") (pinfunction "DI_1") (pintype "input"))
    )
    (net (code "50") (name "Net-(LED12-DO)") (class "Default")
      (node (ref "LED12") (pin "3") (pinfunction "DO_3") (pintype "output"))
      (node (ref "LED13") (pin "1") (pinfunction "DI_1") (pintype "input"))
    )
    (net (code "51") (name "Net-(LED13-DO)") (class "Default")
      (node (ref "LED13") (pin "3") (pinfunction "DO_3") (pintype "output"))
      (node (ref "LED14") (pin "1") (pinfunction "DI_1") (pintype "input"))
    )
    (net (code "52") (name "Net-(LED14-DO)") (class "Default")
      (node (ref "LED14") (pin "3") (pinfunction "DO_3") (pintype "output"))
      (node (ref "LED15") (pin "1") (pinfunction "DI_1") (pintype "input"))
    )
    (net (code "53") (name "Net-(LED15-DO)") (class "Default")
      (node (ref "LED15") (pin "3") (pinfunction "DO_3") (pintype "output"))
      (node (ref "LED16") (pin "1") (pinfunction "DI_1") (pintype "input"))
    )
    (net (code "54") (name "Net-(LED16-DO)") (class "Default")
      (node (ref "LED16") (pin "3") (pinfunction "DO_3") (pintype "output"))
      (node (ref "LED17") (pin "1") (pinfunction "DI_1") (pintype "input"))
    )
    (net (code "55") (name "Net-(LED17-DO)") (class "Default")
      (node (ref "LED17") (pin "3") (pinfunction "DO_3") (pintype "output"))
      (node (ref "LED18") (pin "1") (pinfunction "DI_1") (pintype "input"))
    )
    (net (code "56") (name "Net-(LED18-DO)") (class "Default")
      (node (ref "LED18") (pin "3") (pinfunction "DO_3") (pintype "output"))
      (node (ref "LED19") (pin "1") (pinfunction "DI_1") (pintype "input"))
    )
    (net (code "57") (name "Net-(LED19-DO)") (class "Default")
      (node (ref "LED19") (pin "3") (pinfunction "DO_3") (pintype "output"))
      (node (ref "LED20") (pin "1") (pinfunction "DI_1") (pintype "input"))
    )
    (net (code "58") (name "unconnected-(J1-PadRING2)") (class "Default")
      (node (ref "J1") (pin "RING2") (pinfunction "RING2_RING2") (pintype "bidirectional"))
    )
    (net (code "59") (name "unconnected-(J3-PadRING2)") (class "Default")
      (node (ref "J3") (pin "RING2") (pinfunction "RING2_RING2") (pintype "bidirectional"))
    )
    (net (code "60") (name "unconnected-(LED20-DO-Pad3)") (class "Default")
      (node (ref "LED20") (pin "3") (pinfunction "DO_3") (pintype "output"))
    )
    (net (code "61") (name "unconnected-(U1-3V3_EN-PadP$37)") (class "Default")
      (node (ref "U1") (pin "P$37") (pinfunction "3V3_EN_P$37") (pintype "input"))
    )
    (net (code "62") (name "unconnected-(U1-ADC_REF-PadP$35)") (class "Default")
      (node (ref "U1") (pin "P$35") (pinfunction "ADC_REF_P$35") (pintype "input"))
    )
    (net (code "63") (name "unconnected-(U1-RUN-PadP$30)") (class "Default")
      (node (ref "U1") (pin "P$30") (pinfunction "RUN_P$30") (pintype "input"))
    )
    (net (code "64") (name "unconnected-(U1-SWCLK-PadP$41)") (class "Default")
      (node (ref "U1") (pin "P$41") (pinfunction "SWCLK_P$41") (pintype "input"))
    )
    (net (code "65") (name "unconnected-(U1-SWDIO-PadP$43)") (class "Default")
      (node (ref "U1") (pin "P$43") (pinfunction "SWDIO_P$43") (pintype "bidirectional"))
    )
  )
)
